# bluetooth-v12.net
KiCad netlist of a schematic drawn in EAGLE
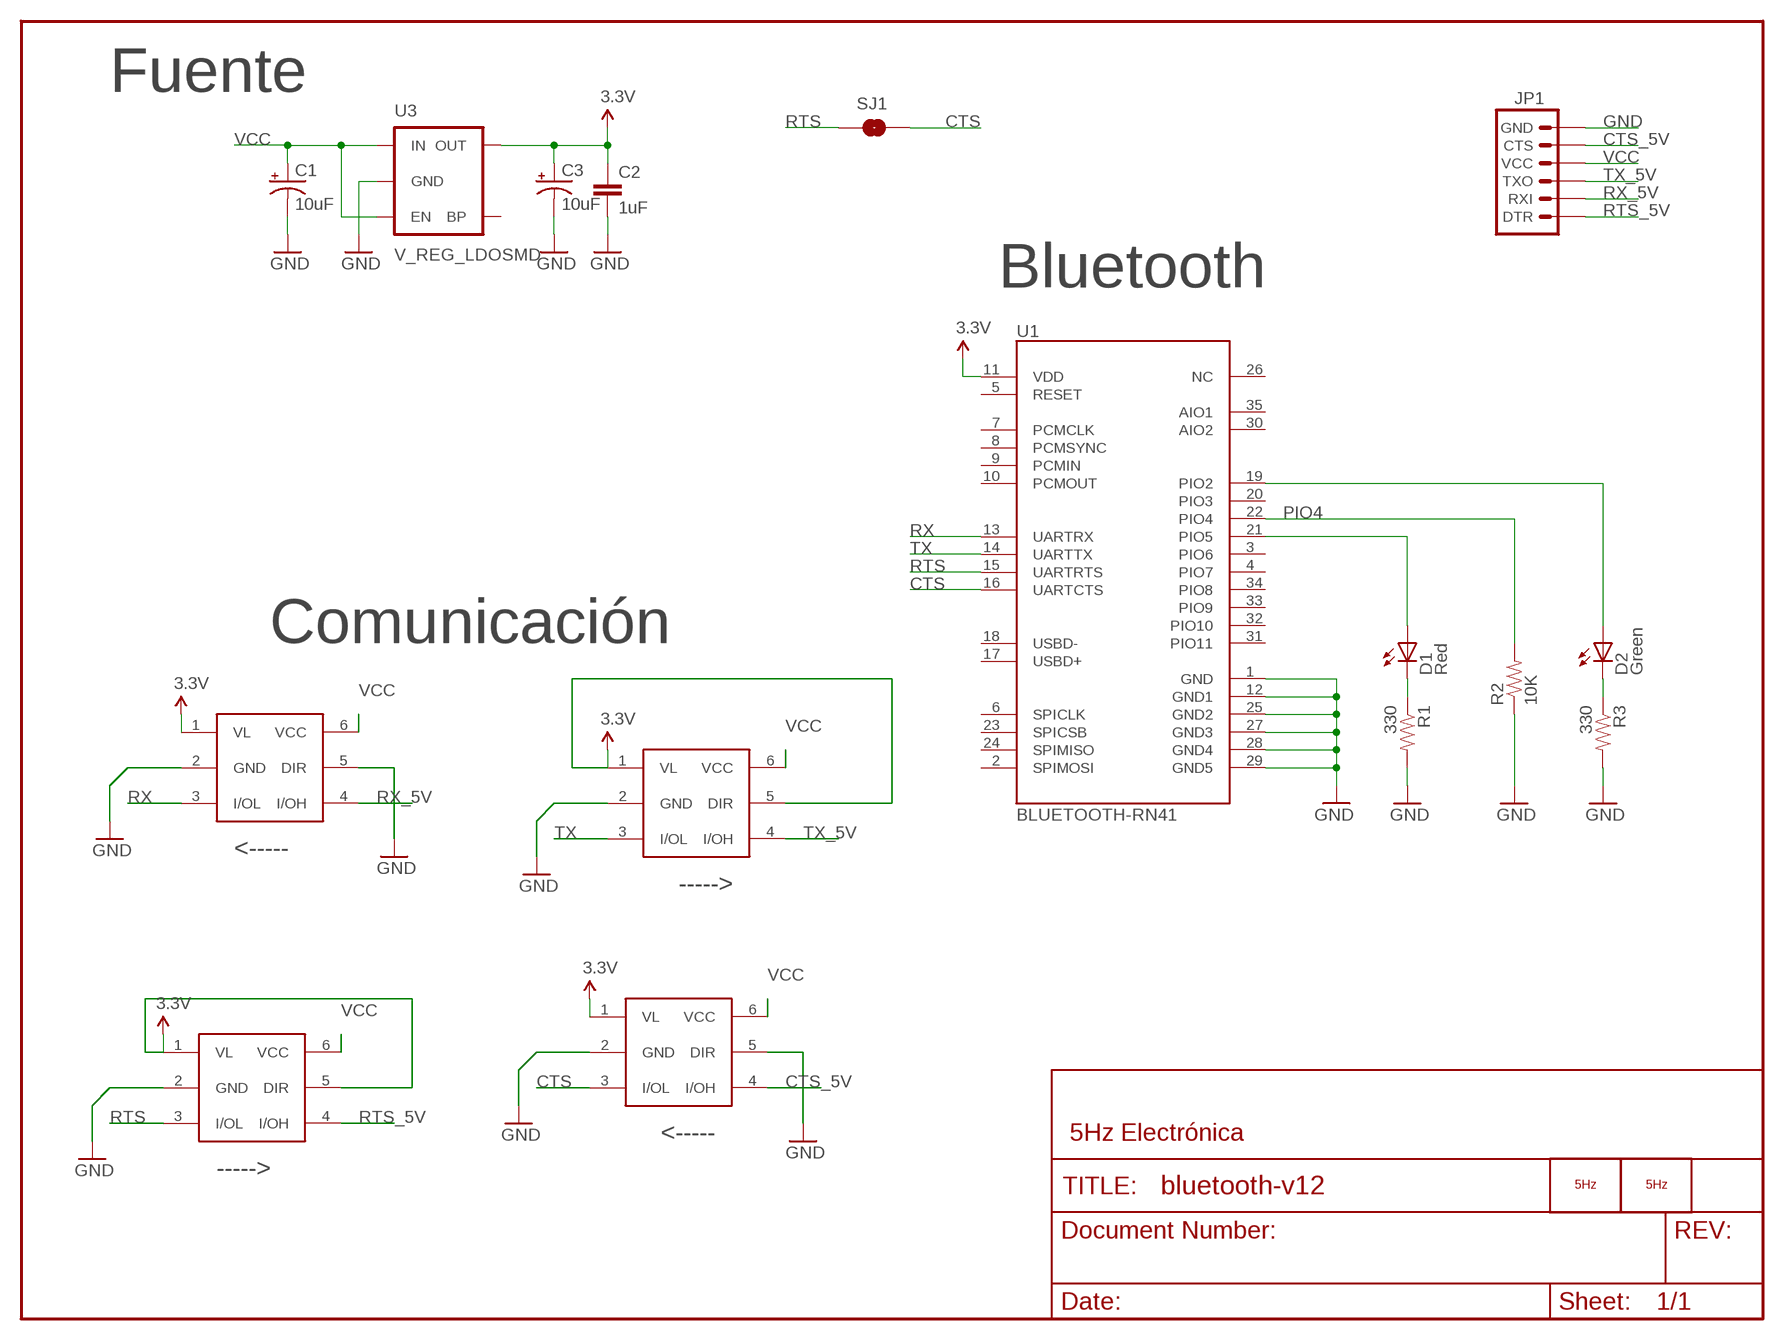
[diagram p0: schematic, sheet 1]

(export (version "E")
  (design (tool "Eeschema 10.0.6"))
  (components
    (comp (ref "C1")
      (value "10uF")
      (footprint "eagle-import:EIA3216")
      (libsource (lib "eagle-import") (part "CAP_POL1206"))
    )
    (comp (ref "C2")
      (value "1uF")
      (footprint "eagle-import:0603-CAP")
      (libsource (lib "eagle-import") (part "CAP0603-CAP"))
    )
    (comp (ref "C3")
      (value "10uF")
      (footprint "eagle-import:EIA3216")
      (libsource (lib "eagle-import") (part "CAP_POL1206"))
    )
    (comp (ref "D1")
      (value "Red")
      (footprint "eagle-import:LED-0603")
      (libsource (lib "eagle-import") (part "LED0603"))
    )
    (comp (ref "D2")
      (value "Green")
      (footprint "eagle-import:LED-0603")
      (libsource (lib "eagle-import") (part "LED0603"))
    )
    (comp (ref "JP1")
      (value "ARDUINO_SERIAL_PROGRAMPTH")
      (footprint "eagle-import:1X06")
      (libsource (lib "eagle-import") (part "ARDUINO_SERIAL_PROGRAMPTH"))
    )
    (comp (ref "LOGO2")
      (value "LOGO_5HZ_H_5MM")
      (footprint "eagle-import:5HZ_LOGO_H_5MM")
      (libsource (lib "eagle-import") (part "LOGO_5HZ_H_5MM"))
    )
    (comp (ref "LOGO3")
      (value "LOGO_5HZ_H_15MM")
      (footprint "eagle-import:5HZ_LOGO_H_15MM")
      (libsource (lib "eagle-import") (part "LOGO_5HZ_H_15MM"))
    )
    (comp (ref "R1")
      (value "330")
      (footprint "eagle-import:0603-RES")
      (libsource (lib "eagle-import") (part "RESISTOR0603-RES"))
    )
    (comp (ref "R2")
      (value "10K")
      (footprint "eagle-import:0603-RES")
      (libsource (lib "eagle-import") (part "RESISTOR0603-RES"))
    )
    (comp (ref "R3")
      (value "330")
      (footprint "eagle-import:0603-RES")
      (libsource (lib "eagle-import") (part "RESISTOR0603-RES"))
    )
    (comp (ref "SJ1")
      (value "SOLDERJUMPERNO")
      (footprint "eagle-import:SJ_2S-NO")
      (libsource (lib "eagle-import") (part "SOLDERJUMPERNO"))
    )
    (comp (ref "U1")
      (value "BLUETOOTH-RN41")
      (footprint "eagle-import:RN41")
      (libsource (lib "eagle-import") (part "BLUETOOTH-RN41{dblquote}"))
    )
    (comp (ref "U2")
      (value "MAX337")
      (footprint "eagle-import:SOT-363")
      (libsource (lib "eagle-import") (part "MAX337"))
    )
    (comp (ref "U3")
      (value "V_REG_LDOSMD")
      (footprint "eagle-import:SOT23-5")
      (libsource (lib "eagle-import") (part "V_REG_LDOSMD"))
    )
    (comp (ref "U4")
      (value "MAX337")
      (footprint "eagle-import:SOT-363")
      (libsource (lib "eagle-import") (part "MAX337"))
    )
    (comp (ref "U5")
      (value "MAX337")
      (footprint "eagle-import:SOT-363")
      (libsource (lib "eagle-import") (part "MAX337"))
    )
    (comp (ref "U6")
      (value "MAX337")
      (footprint "eagle-import:SOT-363")
      (libsource (lib "eagle-import") (part "MAX337"))
    )
  )
  (nets
    (net (code "1") (name "/CTS") (class "Default")
      (node (ref "SJ1") (pin "2") (pinfunction "2_2") (pintype "passive"))
      (node (ref "U1") (pin "16") (pinfunction "UARTCTS_16") (pintype "bidirectional"))
      (node (ref "U2") (pin "3") (pinfunction "I/OL_3") (pintype "bidirectional"))
    )
    (net (code "2") (name "/CTS_5V") (class "Default")
      (node (ref "JP1") (pin "5") (pinfunction "CTS_5") (pintype "passive"))
      (node (ref "U2") (pin "4") (pinfunction "I/OH_4") (pintype "bidirectional"))
    )
    (net (code "3") (name "/PIO4") (class "Default")
      (node (ref "R2") (pin "2") (pinfunction "2_2") (pintype "passive"))
      (node (ref "U1") (pin "22") (pinfunction "PIO4_22") (pintype "bidirectional"))
    )
    (net (code "4") (name "/RTS") (class "Default")
      (node (ref "SJ1") (pin "1") (pinfunction "1_1") (pintype "passive"))
      (node (ref "U1") (pin "15") (pinfunction "UARTRTS_15") (pintype "bidirectional"))
      (node (ref "U5") (pin "3") (pinfunction "I/OL_3") (pintype "bidirectional"))
    )
    (net (code "5") (name "/RTS_5V") (class "Default")
      (node (ref "JP1") (pin "1") (pinfunction "DTR_1") (pintype "passive"))
      (node (ref "U5") (pin "4") (pinfunction "I/OH_4") (pintype "bidirectional"))
    )
    (net (code "6") (name "/RX") (class "Default")
      (node (ref "U1") (pin "13") (pinfunction "UARTRX_13") (pintype "bidirectional"))
      (node (ref "U4") (pin "3") (pinfunction "I/OL_3") (pintype "bidirectional"))
    )
    (net (code "7") (name "/RX_5V") (class "Default")
      (node (ref "JP1") (pin "2") (pinfunction "RXI_2") (pintype "passive"))
      (node (ref "U4") (pin "4") (pinfunction "I/OH_4") (pintype "bidirectional"))
    )
    (net (code "8") (name "/TX") (class "Default")
      (node (ref "U1") (pin "14") (pinfunction "UARTTX_14") (pintype "bidirectional"))
      (node (ref "U6") (pin "3") (pinfunction "I/OL_3") (pintype "bidirectional"))
    )
    (net (code "9") (name "/TX_5V") (class "Default")
      (node (ref "JP1") (pin "3") (pinfunction "TXO_3") (pintype "passive"))
      (node (ref "U6") (pin "4") (pinfunction "I/OH_4") (pintype "bidirectional"))
    )
    (net (code "10") (name "/VCC") (class "Default")
      (node (ref "C1") (pin "A") (pinfunction "+_A") (pintype "passive"))
      (node (ref "JP1") (pin "4") (pinfunction "VCC_4") (pintype "passive"))
      (node (ref "U2") (pin "6") (pinfunction "VCC_6") (pintype "bidirectional"))
      (node (ref "U3") (pin "1") (pinfunction "IN_1") (pintype "input"))
      (node (ref "U3") (pin "3") (pinfunction "EN_3") (pintype "input"))
      (node (ref "U4") (pin "6") (pinfunction "VCC_6") (pintype "bidirectional"))
      (node (ref "U5") (pin "6") (pinfunction "VCC_6") (pintype "bidirectional"))
      (node (ref "U6") (pin "6") (pinfunction "VCC_6") (pintype "bidirectional"))
    )
    (net (code "11") (name "3.3V") (class "Default")
      (node (ref "C2") (pin "1") (pinfunction "1_1") (pintype "passive"))
      (node (ref "C3") (pin "A") (pinfunction "+_A") (pintype "passive"))
      (node (ref "U1") (pin "11") (pinfunction "VDD_11") (pintype "bidirectional"))
      (node (ref "U2") (pin "1") (pinfunction "VL_1") (pintype "bidirectional"))
      (node (ref "U3") (pin "5") (pinfunction "OUT_5") (pintype "passive"))
      (node (ref "U4") (pin "1") (pinfunction "VL_1") (pintype "bidirectional"))
      (node (ref "U5") (pin "1") (pinfunction "VL_1") (pintype "bidirectional"))
      (node (ref "U5") (pin "5") (pinfunction "DIR_5") (pintype "bidirectional"))
      (node (ref "U6") (pin "1") (pinfunction "VL_1") (pintype "bidirectional"))
      (node (ref "U6") (pin "5") (pinfunction "DIR_5") (pintype "bidirectional"))
    )
    (net (code "12") (name "GND") (class "Default")
      (node (ref "C1") (pin "C") (pinfunction "-_C") (pintype "passive"))
      (node (ref "C2") (pin "2") (pinfunction "2_2") (pintype "passive"))
      (node (ref "C3") (pin "C") (pinfunction "-_C") (pintype "passive"))
      (node (ref "JP1") (pin "6") (pinfunction "GND_6") (pintype "passive"))
      (node (ref "R1") (pin "2") (pinfunction "2_2") (pintype "passive"))
      (node (ref "R2") (pin "1") (pinfunction "1_1") (pintype "passive"))
      (node (ref "R3") (pin "2") (pinfunction "2_2") (pintype "passive"))
      (node (ref "U1") (pin "1") (pinfunction "GND_1") (pintype "bidirectional"))
      (node (ref "U1") (pin "12") (pinfunction "GND1_12") (pintype "bidirectional"))
      (node (ref "U1") (pin "25") (pinfunction "GND2_25") (pintype "bidirectional"))
      (node (ref "U1") (pin "27") (pinfunction "GND3_27") (pintype "bidirectional"))
      (node (ref "U1") (pin "28") (pinfunction "GND4_28") (pintype "bidirectional"))
      (node (ref "U1") (pin "29") (pinfunction "GND5_29") (pintype "bidirectional"))
      (node (ref "U2") (pin "2") (pinfunction "GND_2") (pintype "bidirectional"))
      (node (ref "U2") (pin "5") (pinfunction "DIR_5") (pintype "bidirectional"))
      (node (ref "U3") (pin "2") (pinfunction "GND_2") (pintype "input"))
      (node (ref "U4") (pin "2") (pinfunction "GND_2") (pintype "bidirectional"))
      (node (ref "U4") (pin "5") (pinfunction "DIR_5") (pintype "bidirectional"))
      (node (ref "U5") (pin "2") (pinfunction "GND_2") (pintype "bidirectional"))
      (node (ref "U6") (pin "2") (pinfunction "GND_2") (pintype "bidirectional"))
    )
    (net (code "13") (name "Net-(D1-PadC)") (class "Default")
      (node (ref "D1") (pin "C") (pinfunction "C_C") (pintype "passive"))
      (node (ref "R1") (pin "1") (pinfunction "1_1") (pintype "passive"))
    )
    (net (code "14") (name "Net-(D2-PadC)") (class "Default")
      (node (ref "D2") (pin "C") (pinfunction "C_C") (pintype "passive"))
      (node (ref "R3") (pin "1") (pinfunction "1_1") (pintype "passive"))
    )
    (net (code "15") (name "Net-(U1-PIO2)") (class "Default")
      (node (ref "D2") (pin "A") (pinfunction "A_A") (pintype "passive"))
      (node (ref "U1") (pin "19") (pinfunction "PIO2_19") (pintype "bidirectional"))
    )
    (net (code "16") (name "Net-(U1-PIO5)") (class "Default")
      (node (ref "D1") (pin "A") (pinfunction "A_A") (pintype "passive"))
      (node (ref "U1") (pin "21") (pinfunction "PIO5_21") (pintype "bidirectional"))
    )
    (net (code "17") (name "unconnected-(U1-AIO1-Pad35)") (class "Default")
      (node (ref "U1") (pin "35") (pinfunction "AIO1_35") (pintype "bidirectional"))
    )
    (net (code "18") (name "unconnected-(U1-AIO2-Pad30)") (class "Default")
      (node (ref "U1") (pin "30") (pinfunction "AIO2_30") (pintype "bidirectional"))
    )
    (net (code "19") (name "unconnected-(U1-NC-Pad26)") (class "Default")
      (node (ref "U1") (pin "26") (pinfunction "NC_26") (pintype "bidirectional"))
    )
    (net (code "20") (name "unconnected-(U1-PCMCLK-Pad7)") (class "Default")
      (node (ref "U1") (pin "7") (pinfunction "PCMCLK_7") (pintype "bidirectional"))
    )
    (net (code "21") (name "unconnected-(U1-PCMIN-Pad9)") (class "Default")
      (node (ref "U1") (pin "9") (pinfunction "PCMIN_9") (pintype "bidirectional"))
    )
    (net (code "22") (name "unconnected-(U1-PCMOUT-Pad10)") (class "Default")
      (node (ref "U1") (pin "10") (pinfunction "PCMOUT_10") (pintype "bidirectional"))
    )
    (net (code "23") (name "unconnected-(U1-PCMSYNC-Pad8)") (class "Default")
      (node (ref "U1") (pin "8") (pinfunction "PCMSYNC_8") (pintype "bidirectional"))
    )
    (net (code "24") (name "unconnected-(U1-PIO3-Pad20)") (class "Default")
      (node (ref "U1") (pin "20") (pinfunction "PIO3_20") (pintype "bidirectional"))
    )
    (net (code "25") (name "unconnected-(U1-PIO6-Pad3)") (class "Default")
      (node (ref "U1") (pin "3") (pinfunction "PIO6_3") (pintype "bidirectional"))
    )
    (net (code "26") (name "unconnected-(U1-PIO7-Pad4)") (class "Default")
      (node (ref "U1") (pin "4") (pinfunction "PIO7_4") (pintype "bidirectional"))
    )
    (net (code "27") (name "unconnected-(U1-PIO8-Pad34)") (class "Default")
      (node (ref "U1") (pin "34") (pinfunction "PIO8_34") (pintype "bidirectional"))
    )
    (net (code "28") (name "unconnected-(U1-PIO9-Pad33)") (class "Default")
      (node (ref "U1") (pin "33") (pinfunction "PIO9_33") (pintype "bidirectional"))
    )
    (net (code "29") (name "unconnected-(U1-PIO10-Pad32)") (class "Default")
      (node (ref "U1") (pin "32") (pinfunction "PIO10_32") (pintype "bidirectional"))
    )
    (net (code "30") (name "unconnected-(U1-PIO11-Pad31)") (class "Default")
      (node (ref "U1") (pin "31") (pinfunction "PIO11_31") (pintype "bidirectional"))
    )
    (net (code "31") (name "unconnected-(U1-RESET-Pad5)") (class "Default")
      (node (ref "U1") (pin "5") (pinfunction "RESET_5") (pintype "bidirectional"))
    )
    (net (code "32") (name "unconnected-(U1-SPICLK-Pad6)") (class "Default")
      (node (ref "U1") (pin "6") (pinfunction "SPICLK_6") (pintype "bidirectional"))
    )
    (net (code "33") (name "unconnected-(U1-SPICSB-Pad23)") (class "Default")
      (node (ref "U1") (pin "23") (pinfunction "SPICSB_23") (pintype "bidirectional"))
    )
    (net (code "34") (name "unconnected-(U1-SPIMISO-Pad24)") (class "Default")
      (node (ref "U1") (pin "24") (pinfunction "SPIMISO_24") (pintype "bidirectional"))
    )
    (net (code "35") (name "unconnected-(U1-SPIMOSI-Pad2)") (class "Default")
      (node (ref "U1") (pin "2") (pinfunction "SPIMOSI_2") (pintype "bidirectional"))
    )
    (net (code "36") (name "unconnected-(U1-USBD+-Pad17)") (class "Default")
      (node (ref "U1") (pin "17") (pinfunction "USBD+_17") (pintype "bidirectional"))
    )
    (net (code "37") (name "unconnected-(U1-USBD--Pad18)") (class "Default")
      (node (ref "U1") (pin "18") (pinfunction "USBD-_18") (pintype "bidirectional"))
    )
    (net (code "38") (name "unconnected-(U3-BP-Pad4)") (class "Default")
      (node (ref "U3") (pin "4") (pinfunction "BP_4") (pintype "input"))
    )
  )
)
